# EchoFlex-ArduinoNanoSense-V1.net
KiCad netlist of a schematic drawn in EAGLE
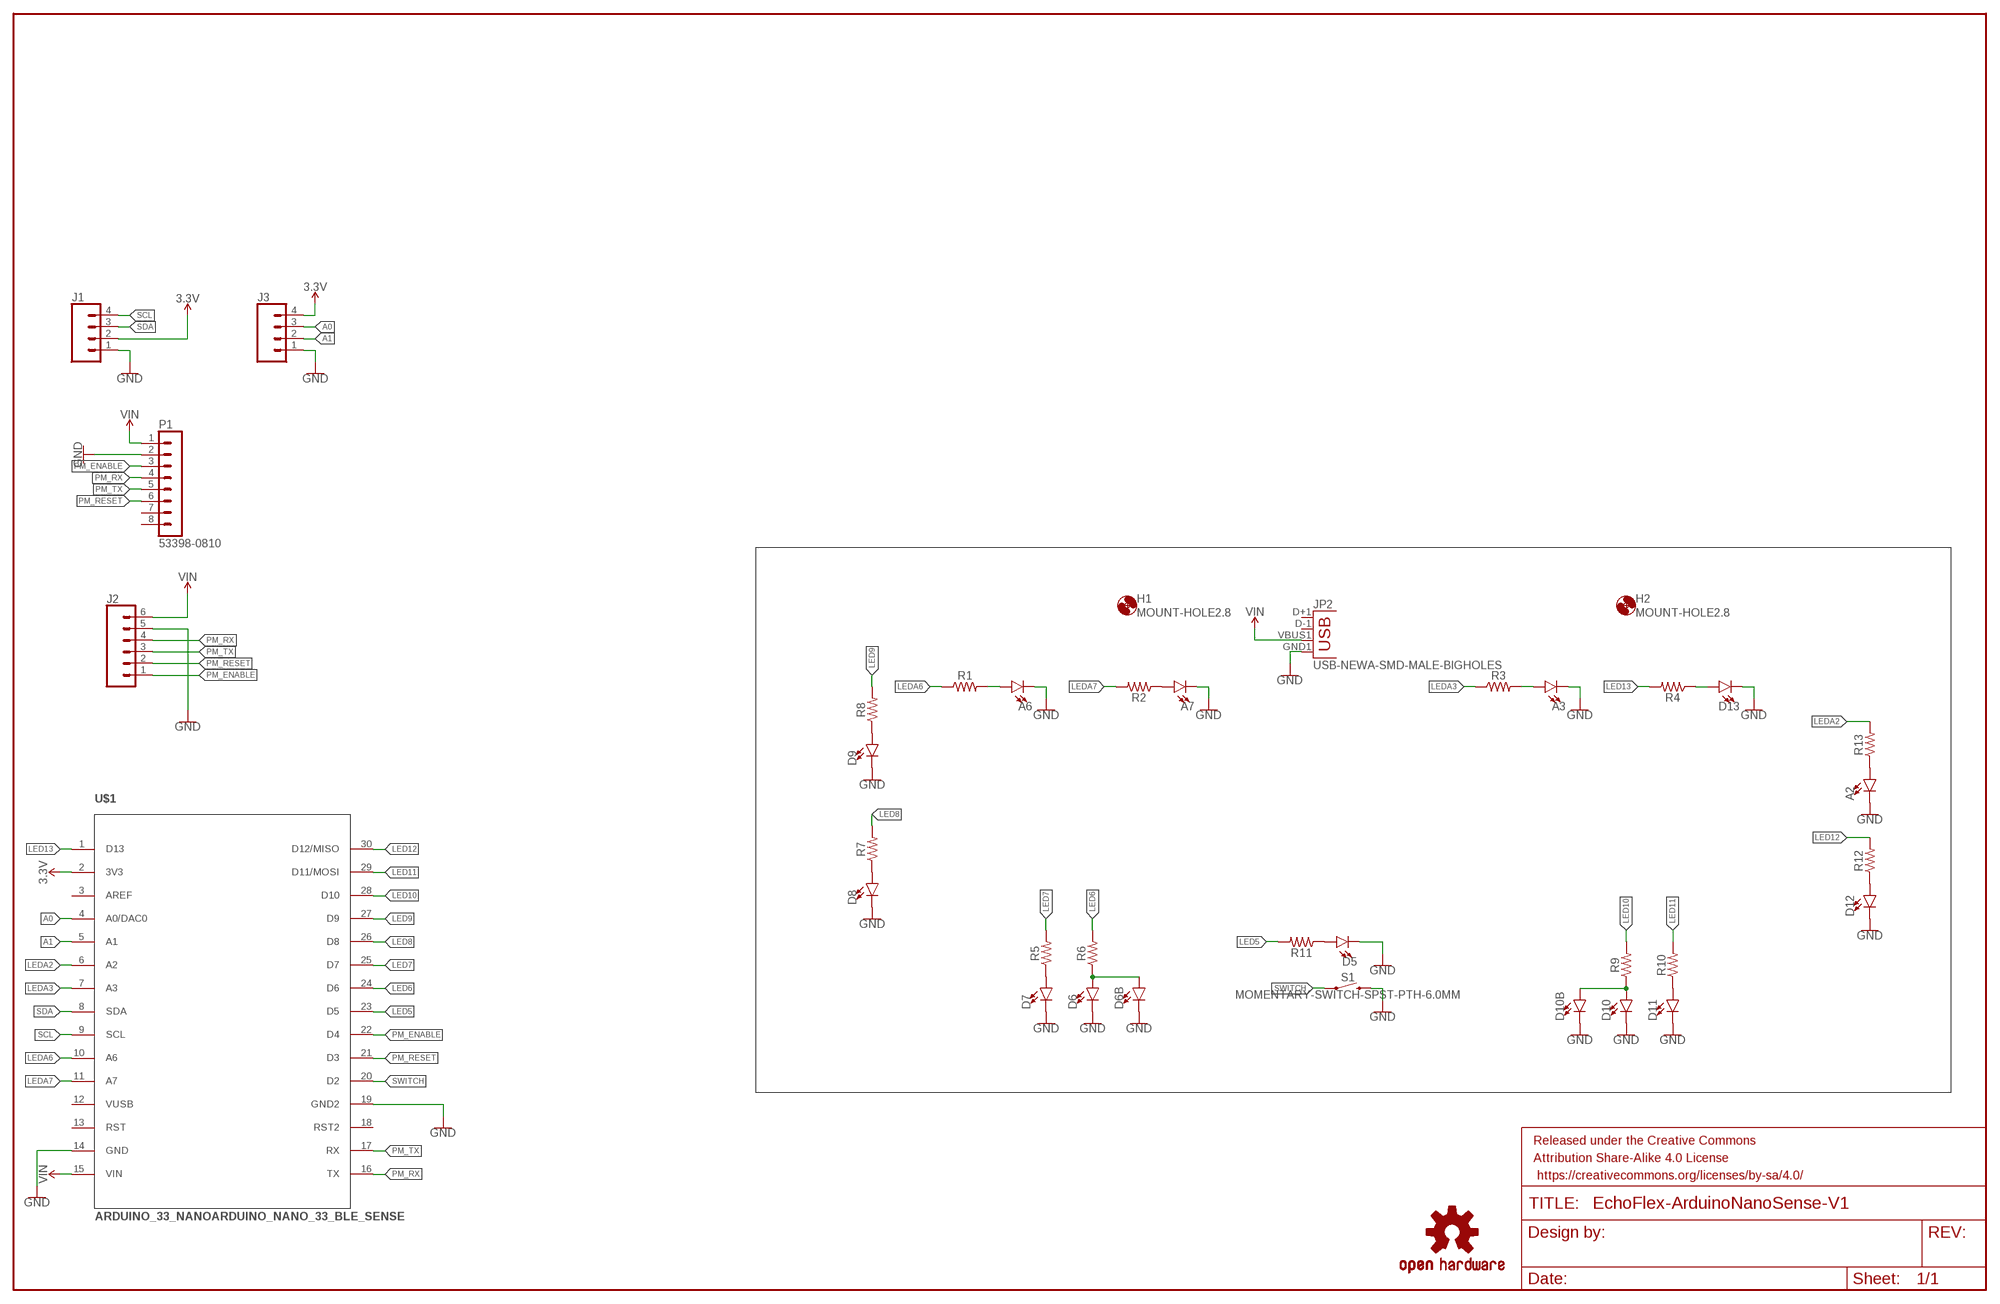
[diagram p0: schematic, sheet 1]

(export (version "E")
  (design (tool "Eeschema 10.0.6"))
  (components
    (comp (ref "A2")
      (value "LED1206")
      (footprint "eagle-import:LED-1206")
      (libsource (lib "eagle-import") (part "LED1206"))
    )
    (comp (ref "A3")
      (value "LED1206")
      (footprint "eagle-import:LED-1206")
      (libsource (lib "eagle-import") (part "LED1206"))
    )
    (comp (ref "A6")
      (value "LED1206")
      (footprint "eagle-import:LED-1206")
      (libsource (lib "eagle-import") (part "LED1206"))
    )
    (comp (ref "A7")
      (value "LED1206")
      (footprint "eagle-import:LED-1206")
      (libsource (lib "eagle-import") (part "LED1206"))
    )
    (comp (ref "D5")
      (value "LED1206")
      (footprint "eagle-import:LED-1206")
      (libsource (lib "eagle-import") (part "LED1206"))
    )
    (comp (ref "D6")
      (value "LED1206")
      (footprint "eagle-import:LED-1206")
      (libsource (lib "eagle-import") (part "LED1206"))
    )
    (comp (ref "D6B")
      (value "LED1206")
      (footprint "eagle-import:LED-1206")
      (libsource (lib "eagle-import") (part "LED1206"))
    )
    (comp (ref "D7")
      (value "LED1206")
      (footprint "eagle-import:LED-1206")
      (libsource (lib "eagle-import") (part "LED1206"))
    )
    (comp (ref "D8")
      (value "LED1206")
      (footprint "eagle-import:LED-1206")
      (libsource (lib "eagle-import") (part "LED1206"))
    )
    (comp (ref "D9")
      (value "LED1206")
      (footprint "eagle-import:LED-1206")
      (libsource (lib "eagle-import") (part "LED1206"))
    )
    (comp (ref "D10")
      (value "LED1206")
      (footprint "eagle-import:LED-1206")
      (libsource (lib "eagle-import") (part "LED1206"))
    )
    (comp (ref "D10B")
      (value "LED1206")
      (footprint "eagle-import:LED-1206")
      (libsource (lib "eagle-import") (part "LED1206"))
    )
    (comp (ref "D11")
      (value "LED1206")
      (footprint "eagle-import:LED-1206")
      (libsource (lib "eagle-import") (part "LED1206"))
    )
    (comp (ref "D12")
      (value "LED1206")
      (footprint "eagle-import:LED-1206")
      (libsource (lib "eagle-import") (part "LED1206"))
    )
    (comp (ref "D13")
      (value "LED1206")
      (footprint "eagle-import:LED-1206")
      (libsource (lib "eagle-import") (part "LED1206"))
    )
    (comp (ref "FRAME1")
      (value "FRAME-LEDGER")
      (footprint "eagle-import:CREATIVE_COMMONS")
      (libsource (lib "eagle-import") (part "FRAME-LEDGER"))
    )
    (comp (ref "H1")
      (value "MOUNT-HOLE2.8")
      (footprint "eagle-import:2,8")
      (libsource (lib "eagle-import") (part "MOUNT-HOLE2.8"))
    )
    (comp (ref "H2")
      (value "MOUNT-HOLE2.8")
      (footprint "eagle-import:2,8")
      (libsource (lib "eagle-import") (part "MOUNT-HOLE2.8"))
    )
    (comp (ref "J1")
      (value "CONN_04SMD2")
      (footprint "eagle-import:JST04_1MM_RA")
      (libsource (lib "eagle-import") (part "CONN_04SMD2"))
    )
    (comp (ref "J2")
      (value "CONN_06SILK_FEMALE_PTH")
      (footprint "eagle-import:1X06")
      (libsource (lib "eagle-import") (part "CONN_06SILK_FEMALE_PTH"))
    )
    (comp (ref "J3")
      (value "CONN_04")
      (footprint "eagle-import:1X04")
      (libsource (lib "eagle-import") (part "CONN_04"))
    )
    (comp (ref "JP2")
      (value "USB-NEWA-SMD-MALE-BIGHOLES")
      (footprint "eagle-import:USB-A-SMT-MALE")
      (libsource (lib "eagle-import") (part "USB-NEWA-SMD-MALE-BIGHOLES"))
    )
    (comp (ref "LOGO1")
      (value "OSHW-LOGOM")
      (footprint "eagle-import:OSHW-LOGO-M")
      (libsource (lib "eagle-import") (part "OSHW-LOGOM"))
    )
    (comp (ref "P1")
      (value "53398-0810")
      (footprint "eagle-import:53398-0810")
      (libsource (lib "eagle-import") (part "53398-0810"))
    )
    (comp (ref "R1")
      (value "RESISTOR0805")
      (footprint "eagle-import:0805")
      (libsource (lib "eagle-import") (part "RESISTOR0805"))
    )
    (comp (ref "R2")
      (value "RESISTOR0805")
      (footprint "eagle-import:0805")
      (libsource (lib "eagle-import") (part "RESISTOR0805"))
    )
    (comp (ref "R3")
      (value "RESISTOR0805")
      (footprint "eagle-import:0805")
      (libsource (lib "eagle-import") (part "RESISTOR0805"))
    )
    (comp (ref "R4")
      (value "RESISTOR0805")
      (footprint "eagle-import:0805")
      (libsource (lib "eagle-import") (part "RESISTOR0805"))
    )
    (comp (ref "R5")
      (value "RESISTOR0805")
      (footprint "eagle-import:0805")
      (libsource (lib "eagle-import") (part "RESISTOR0805"))
    )
    (comp (ref "R6")
      (value "RESISTOR0805")
      (footprint "eagle-import:0805")
      (libsource (lib "eagle-import") (part "RESISTOR0805"))
    )
    (comp (ref "R7")
      (value "RESISTOR0805")
      (footprint "eagle-import:0805")
      (libsource (lib "eagle-import") (part "RESISTOR0805"))
    )
    (comp (ref "R8")
      (value "RESISTOR0805")
      (footprint "eagle-import:0805")
      (libsource (lib "eagle-import") (part "RESISTOR0805"))
    )
    (comp (ref "R9")
      (value "RESISTOR0805")
      (footprint "eagle-import:0805")
      (libsource (lib "eagle-import") (part "RESISTOR0805"))
    )
    (comp (ref "R10")
      (value "RESISTOR0805")
      (footprint "eagle-import:0805")
      (libsource (lib "eagle-import") (part "RESISTOR0805"))
    )
    (comp (ref "R11")
      (value "RESISTOR0805")
      (footprint "eagle-import:0805")
      (libsource (lib "eagle-import") (part "RESISTOR0805"))
    )
    (comp (ref "R12")
      (value "RESISTOR0805")
      (footprint "eagle-import:0805")
      (libsource (lib "eagle-import") (part "RESISTOR0805"))
    )
    (comp (ref "R13")
      (value "RESISTOR0805")
      (footprint "eagle-import:0805")
      (libsource (lib "eagle-import") (part "RESISTOR0805"))
    )
    (comp (ref "S1")
      (value "MOMENTARY-SWITCH-SPST-PTH-6.0MM")
      (footprint "eagle-import:TACTILE_SWITCH_PTH_6.0MM")
      (libsource (lib "eagle-import") (part "MOMENTARY-SWITCH-SPST-PTH-6.0MM"))
    )
    (comp (ref "U$1")
      (value "ARDUINO_33_NANOARDUINO_NANO_33_BLE_SENSE")
      (footprint "eagle-import:ARDUINO_NANO_33")
      (libsource (lib "eagle-import") (part "ARDUINO_33_NANOARDUINO_NANO_33_BLE_SENSE"))
    )
  )
  (nets
    (net (code "1") (name "/VUSB") (class "Default")
      (node (ref "U$1") (pin "12") (pinfunction "VUSB_12") (pintype "power_in"))
    )
    (net (code "2") (name "3.3V") (class "Default")
      (node (ref "J1") (pin "2") (pinfunction "2_2") (pintype "passive"))
      (node (ref "J3") (pin "4") (pinfunction "4_4") (pintype "passive"))
      (node (ref "U$1") (pin "2") (pinfunction "3V3_2") (pintype "power_in"))
    )
    (net (code "3") (name "A0") (class "Default")
      (node (ref "J3") (pin "3") (pinfunction "3_3") (pintype "passive"))
      (node (ref "U$1") (pin "4") (pinfunction "A0/DAC0_4") (pintype "bidirectional"))
    )
    (net (code "4") (name "A1") (class "Default")
      (node (ref "J3") (pin "2") (pinfunction "2_2") (pintype "passive"))
      (node (ref "U$1") (pin "5") (pinfunction "A1_5") (pintype "bidirectional"))
    )
    (net (code "5") (name "GND") (class "Default")
      (node (ref "A2") (pin "C") (pinfunction "C_C") (pintype "passive"))
      (node (ref "A3") (pin "C") (pinfunction "C_C") (pintype "passive"))
      (node (ref "A6") (pin "C") (pinfunction "C_C") (pintype "passive"))
      (node (ref "A7") (pin "C") (pinfunction "C_C") (pintype "passive"))
      (node (ref "D10") (pin "C") (pinfunction "C_C") (pintype "passive"))
      (node (ref "D10B") (pin "C") (pinfunction "C_C") (pintype "passive"))
      (node (ref "D11") (pin "C") (pinfunction "C_C") (pintype "passive"))
      (node (ref "D12") (pin "C") (pinfunction "C_C") (pintype "passive"))
      (node (ref "D13") (pin "C") (pinfunction "C_C") (pintype "passive"))
      (node (ref "D5") (pin "C") (pinfunction "C_C") (pintype "passive"))
      (node (ref "D6") (pin "C") (pinfunction "C_C") (pintype "passive"))
      (node (ref "D6B") (pin "C") (pinfunction "C_C") (pintype "passive"))
      (node (ref "D7") (pin "C") (pinfunction "C_C") (pintype "passive"))
      (node (ref "D8") (pin "C") (pinfunction "C_C") (pintype "passive"))
      (node (ref "D9") (pin "C") (pinfunction "C_C") (pintype "passive"))
      (node (ref "J1") (pin "1") (pinfunction "1_1") (pintype "passive"))
      (node (ref "J2") (pin "5") (pinfunction "5_5") (pintype "passive"))
      (node (ref "J3") (pin "1") (pinfunction "1_1") (pintype "passive"))
      (node (ref "JP2") (pin "GND1") (pinfunction "GND_GND1") (pintype "bidirectional"))
      (node (ref "P1") (pin "2") (pinfunction "2_2") (pintype "passive"))
      (node (ref "S1") (pin "3") (pinfunction "2_3") (pintype "passive"))
      (node (ref "U$1") (pin "14") (pinfunction "GND_14") (pintype "bidirectional"))
      (node (ref "U$1") (pin "19") (pinfunction "GND2_19") (pintype "bidirectional"))
    )
    (net (code "6") (name "LED5") (class "Default")
      (node (ref "R11") (pin "2") (pinfunction "2_2") (pintype "passive"))
      (node (ref "U$1") (pin "23") (pinfunction "D5_23") (pintype "bidirectional"))
    )
    (net (code "7") (name "LED6") (class "Default")
      (node (ref "R6") (pin "2") (pinfunction "2_2") (pintype "passive"))
      (node (ref "U$1") (pin "24") (pinfunction "D6_24") (pintype "bidirectional"))
    )
    (net (code "8") (name "LED7") (class "Default")
      (node (ref "R5") (pin "2") (pinfunction "2_2") (pintype "passive"))
      (node (ref "U$1") (pin "25") (pinfunction "D7_25") (pintype "bidirectional"))
    )
    (net (code "9") (name "LED8") (class "Default")
      (node (ref "R7") (pin "2") (pinfunction "2_2") (pintype "passive"))
      (node (ref "U$1") (pin "26") (pinfunction "D8_26") (pintype "bidirectional"))
    )
    (net (code "10") (name "LED9") (class "Default")
      (node (ref "R8") (pin "2") (pinfunction "2_2") (pintype "passive"))
      (node (ref "U$1") (pin "27") (pinfunction "D9_27") (pintype "bidirectional"))
    )
    (net (code "11") (name "LED10") (class "Default")
      (node (ref "R9") (pin "2") (pinfunction "2_2") (pintype "passive"))
      (node (ref "U$1") (pin "28") (pinfunction "D10_28") (pintype "bidirectional"))
    )
    (net (code "12") (name "LED11") (class "Default")
      (node (ref "R10") (pin "2") (pinfunction "2_2") (pintype "passive"))
      (node (ref "U$1") (pin "29") (pinfunction "D11/MOSI_29") (pintype "bidirectional"))
    )
    (net (code "13") (name "LED12") (class "Default")
      (node (ref "R12") (pin "2") (pinfunction "2_2") (pintype "passive"))
      (node (ref "U$1") (pin "30") (pinfunction "D12/MISO_30") (pintype "bidirectional"))
    )
    (net (code "14") (name "LED13") (class "Default")
      (node (ref "R4") (pin "2") (pinfunction "2_2") (pintype "passive"))
      (node (ref "U$1") (pin "1") (pinfunction "D13_1") (pintype "bidirectional"))
    )
    (net (code "15") (name "LEDA2") (class "Default")
      (node (ref "R13") (pin "2") (pinfunction "2_2") (pintype "passive"))
      (node (ref "U$1") (pin "6") (pinfunction "A2_6") (pintype "bidirectional"))
    )
    (net (code "16") (name "LEDA3") (class "Default")
      (node (ref "R3") (pin "1") (pinfunction "1_1") (pintype "passive"))
      (node (ref "U$1") (pin "7") (pinfunction "A3_7") (pintype "bidirectional"))
    )
    (net (code "17") (name "LEDA6") (class "Default")
      (node (ref "R1") (pin "1") (pinfunction "1_1") (pintype "passive"))
      (node (ref "U$1") (pin "10") (pinfunction "A6_10") (pintype "bidirectional"))
    )
    (net (code "18") (name "LEDA7") (class "Default")
      (node (ref "R2") (pin "2") (pinfunction "2_2") (pintype "passive"))
      (node (ref "U$1") (pin "11") (pinfunction "A7_11") (pintype "bidirectional"))
    )
    (net (code "19") (name "Net-(A2-PadA)") (class "Default")
      (node (ref "A2") (pin "A") (pinfunction "A_A") (pintype "passive"))
      (node (ref "R13") (pin "1") (pinfunction "1_1") (pintype "passive"))
    )
    (net (code "20") (name "Net-(A3-PadA)") (class "Default")
      (node (ref "A3") (pin "A") (pinfunction "A_A") (pintype "passive"))
      (node (ref "R3") (pin "2") (pinfunction "2_2") (pintype "passive"))
    )
    (net (code "21") (name "Net-(A6-PadA)") (class "Default")
      (node (ref "A6") (pin "A") (pinfunction "A_A") (pintype "passive"))
      (node (ref "R1") (pin "2") (pinfunction "2_2") (pintype "passive"))
    )
    (net (code "22") (name "Net-(A7-PadA)") (class "Default")
      (node (ref "A7") (pin "A") (pinfunction "A_A") (pintype "passive"))
      (node (ref "R2") (pin "1") (pinfunction "1_1") (pintype "passive"))
    )
    (net (code "23") (name "Net-(D5-PadA)") (class "Default")
      (node (ref "D5") (pin "A") (pinfunction "A_A") (pintype "passive"))
      (node (ref "R11") (pin "1") (pinfunction "1_1") (pintype "passive"))
    )
    (net (code "24") (name "Net-(D6-PadA)") (class "Default")
      (node (ref "D6") (pin "A") (pinfunction "A_A") (pintype "passive"))
      (node (ref "D6B") (pin "A") (pinfunction "A_A") (pintype "passive"))
      (node (ref "R6") (pin "1") (pinfunction "1_1") (pintype "passive"))
    )
    (net (code "25") (name "Net-(D7-PadA)") (class "Default")
      (node (ref "D7") (pin "A") (pinfunction "A_A") (pintype "passive"))
      (node (ref "R5") (pin "1") (pinfunction "1_1") (pintype "passive"))
    )
    (net (code "26") (name "Net-(D8-PadA)") (class "Default")
      (node (ref "D8") (pin "A") (pinfunction "A_A") (pintype "passive"))
      (node (ref "R7") (pin "1") (pinfunction "1_1") (pintype "passive"))
    )
    (net (code "27") (name "Net-(D9-PadA)") (class "Default")
      (node (ref "D9") (pin "A") (pinfunction "A_A") (pintype "passive"))
      (node (ref "R8") (pin "1") (pinfunction "1_1") (pintype "passive"))
    )
    (net (code "28") (name "Net-(D10-PadA)") (class "Default")
      (node (ref "D10") (pin "A") (pinfunction "A_A") (pintype "passive"))
      (node (ref "D10B") (pin "A") (pinfunction "A_A") (pintype "passive"))
      (node (ref "R9") (pin "1") (pinfunction "1_1") (pintype "passive"))
    )
    (net (code "29") (name "Net-(D11-PadA)") (class "Default")
      (node (ref "D11") (pin "A") (pinfunction "A_A") (pintype "passive"))
      (node (ref "R10") (pin "1") (pinfunction "1_1") (pintype "passive"))
    )
    (net (code "30") (name "Net-(D12-PadA)") (class "Default")
      (node (ref "D12") (pin "A") (pinfunction "A_A") (pintype "passive"))
      (node (ref "R12") (pin "1") (pinfunction "1_1") (pintype "passive"))
    )
    (net (code "31") (name "Net-(D13-PadA)") (class "Default")
      (node (ref "D13") (pin "A") (pinfunction "A_A") (pintype "passive"))
      (node (ref "R4") (pin "1") (pinfunction "1_1") (pintype "passive"))
    )
    (net (code "32") (name "PM_ENABLE") (class "Default")
      (node (ref "J2") (pin "1") (pinfunction "1_1") (pintype "passive"))
      (node (ref "P1") (pin "3") (pinfunction "3_3") (pintype "passive"))
      (node (ref "U$1") (pin "22") (pinfunction "D4_22") (pintype "bidirectional"))
    )
    (net (code "33") (name "PM_RESET") (class "Default")
      (node (ref "J2") (pin "2") (pinfunction "2_2") (pintype "passive"))
      (node (ref "P1") (pin "6") (pinfunction "6_6") (pintype "passive"))
      (node (ref "U$1") (pin "21") (pinfunction "D3_21") (pintype "bidirectional"))
    )
    (net (code "34") (name "PM_RX") (class "Default")
      (node (ref "J2") (pin "4") (pinfunction "4_4") (pintype "passive"))
      (node (ref "P1") (pin "4") (pinfunction "4_4") (pintype "passive"))
      (node (ref "U$1") (pin "16") (pinfunction "TX_16") (pintype "bidirectional"))
    )
    (net (code "35") (name "PM_TX") (class "Default")
      (node (ref "J2") (pin "3") (pinfunction "3_3") (pintype "passive"))
      (node (ref "P1") (pin "5") (pinfunction "5_5") (pintype "passive"))
      (node (ref "U$1") (pin "17") (pinfunction "RX_17") (pintype "bidirectional"))
    )
    (net (code "36") (name "SCL") (class "Default")
      (node (ref "J1") (pin "4") (pinfunction "4_4") (pintype "passive"))
      (node (ref "U$1") (pin "9") (pinfunction "SCL_9") (pintype "bidirectional"))
    )
    (net (code "37") (name "SDA") (class "Default")
      (node (ref "J1") (pin "3") (pinfunction "3_3") (pintype "passive"))
      (node (ref "U$1") (pin "8") (pinfunction "SDA_8") (pintype "bidirectional"))
    )
    (net (code "38") (name "SWITCH") (class "Default")
      (node (ref "S1") (pin "1") (pinfunction "1_1") (pintype "passive"))
      (node (ref "U$1") (pin "20") (pinfunction "D2_20") (pintype "bidirectional"))
    )
    (net (code "39") (name "VIN") (class "Default")
      (node (ref "J2") (pin "6") (pinfunction "6_6") (pintype "passive"))
      (node (ref "JP2") (pin "VBUS1") (pinfunction "VBUS_VBUS1") (pintype "bidirectional"))
      (node (ref "P1") (pin "1") (pinfunction "1_1") (pintype "passive"))
      (node (ref "U$1") (pin "15") (pinfunction "VIN_15") (pintype "power_in"))
    )
    (net (code "40") (name "unconnected-(JP2-D+-PadD+1)") (class "Default")
      (node (ref "JP2") (pin "D+1") (pinfunction "D+_D+1") (pintype "bidirectional"))
    )
    (net (code "41") (name "unconnected-(JP2-D--PadD-1)") (class "Default")
      (node (ref "JP2") (pin "D-1") (pinfunction "D-_D-1") (pintype "bidirectional"))
    )
    (net (code "42") (name "unconnected-(P1-Pad7)") (class "Default")
      (node (ref "P1") (pin "7") (pinfunction "7_7") (pintype "passive"))
    )
    (net (code "43") (name "unconnected-(P1-Pad8)") (class "Default")
      (node (ref "P1") (pin "8") (pinfunction "8_8") (pintype "passive"))
    )
    (net (code "44") (name "unconnected-(U$1-AREF-Pad3)") (class "Default")
      (node (ref "U$1") (pin "3") (pinfunction "AREF_3") (pintype "output"))
    )
    (net (code "45") (name "unconnected-(U$1-RST-Pad13)") (class "Default")
      (node (ref "U$1") (pin "13") (pinfunction "RST_13") (pintype "bidirectional"))
    )
    (net (code "46") (name "unconnected-(U$1-RST2-Pad18)") (class "Default")
      (node (ref "U$1") (pin "18") (pinfunction "RST2_18") (pintype "bidirectional"))
    )
  )
)
